# Breakouts0.net
KiCad netlist of a schematic drawn in EAGLE
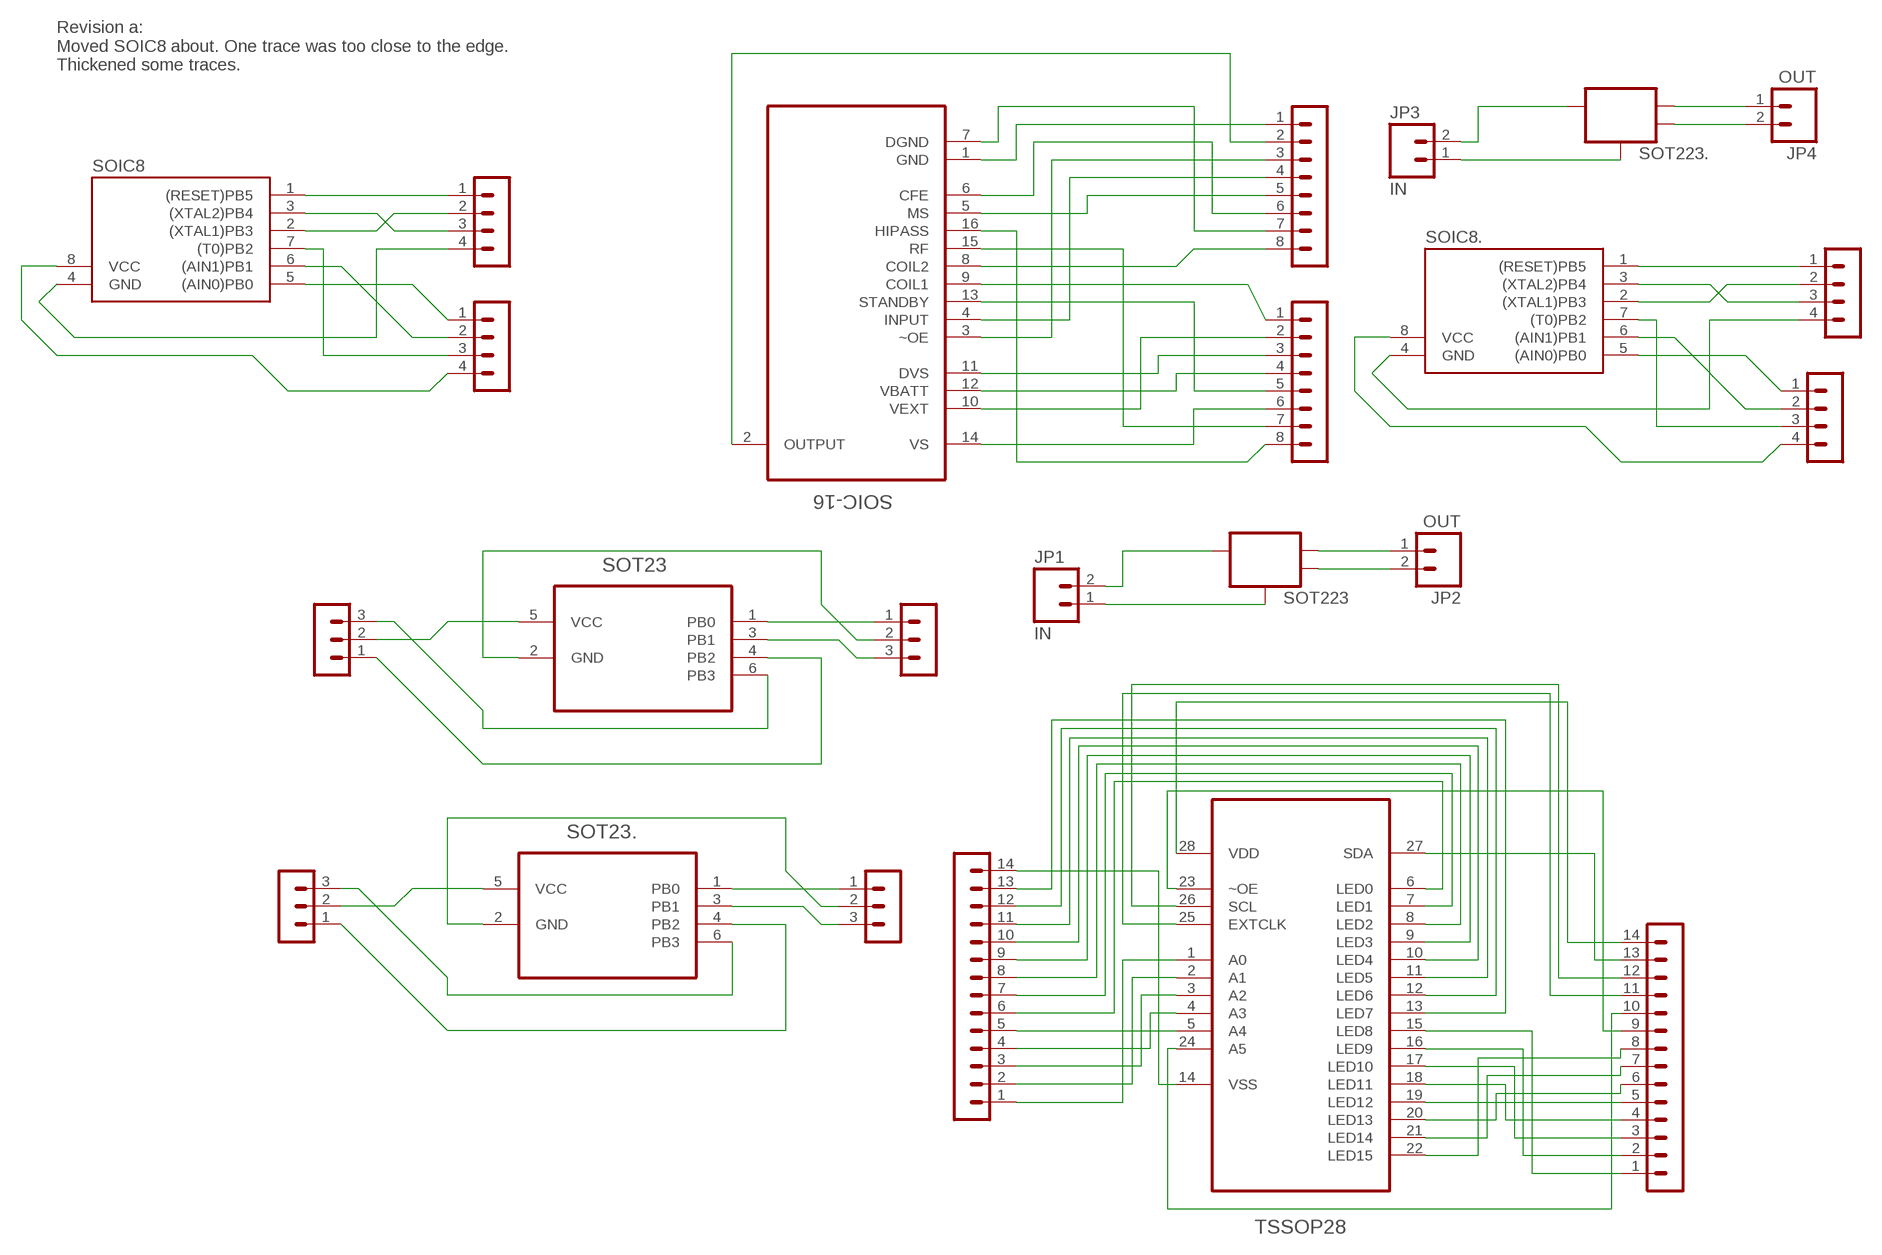
[diagram p0: schematic, sheet 1]

(export (version "E")
  (design (tool "Eeschema 10.0.6"))
  (components
    (comp (ref "JP1")
      (value "IN")
      (footprint "eagle-import:1X02")
      (libsource (lib "eagle-import") (part "M02PTH"))
    )
    (comp (ref "JP2")
      (value "OUT")
      (footprint "eagle-import:1X02")
      (libsource (lib "eagle-import") (part "M02PTH"))
    )
    (comp (ref "JP3")
      (value "IN")
      (footprint "eagle-import:1X02")
      (libsource (lib "eagle-import") (part "M02PTH"))
    )
    (comp (ref "JP4")
      (value "OUT")
      (footprint "eagle-import:1X02")
      (libsource (lib "eagle-import") (part "M02PTH"))
    )
    (comp (ref "SOIC-16")
      (value "U2270B-MFPY")
      (footprint "eagle-import:SOIC127P600X140-16N")
      (libsource (lib "eagle-import") (part "U2270B-MFPY"))
    )
    (comp (ref "SOIC8")
      (value "TINY10S")
      (footprint "eagle-import:SOIC8")
      (libsource (lib "eagle-import") (part "TINY10S"))
    )
    (comp (ref "SOIC8.")
      (value "TINY10S")
      (footprint "eagle-import:SOIC8")
      (libsource (lib "eagle-import") (part "TINY10S"))
    )
    (comp (ref "SOT23")
      (value "ATTINY10-TSHR")
      (footprint "eagle-import:SOT95P280X145-6N")
      (libsource (lib "eagle-import") (part "ATTINY10-TSHR"))
    )
    (comp (ref "SOT23.")
      (value "ATTINY10-TSHR")
      (footprint "eagle-import:SOT95P280X145-6N")
      (libsource (lib "eagle-import") (part "ATTINY10-TSHR"))
    )
    (comp (ref "SOT223")
      (value "SOT223SOT223")
      (footprint "eagle-import:SOT223")
      (libsource (lib "eagle-import") (part "SOT223SOT223"))
    )
    (comp (ref "SOT223.")
      (value "SOT223SOT223")
      (footprint "eagle-import:SOT223")
      (libsource (lib "eagle-import") (part "SOT223SOT223"))
    )
    (comp (ref "SV1")
      (value "MA08-1")
      (footprint "eagle-import:MA08-1")
      (libsource (lib "eagle-import") (part "MA08-1"))
    )
    (comp (ref "SV2")
      (value "MA08-1")
      (footprint "eagle-import:MA08-1")
      (libsource (lib "eagle-import") (part "MA08-1"))
    )
    (comp (ref "SV3")
      (value "MA03-1")
      (footprint "eagle-import:MA03-1")
      (libsource (lib "eagle-import") (part "MA03-1"))
    )
    (comp (ref "SV4")
      (value "MA03-1")
      (footprint "eagle-import:MA03-1")
      (libsource (lib "eagle-import") (part "MA03-1"))
    )
    (comp (ref "SV5")
      (value "MA14-1")
      (footprint "eagle-import:MA14-1")
      (libsource (lib "eagle-import") (part "MA14-1"))
    )
    (comp (ref "SV8")
      (value "MA04-1")
      (footprint "eagle-import:MA04-1")
      (libsource (lib "eagle-import") (part "MA04-1"))
    )
    (comp (ref "SV9")
      (value "MA14-1")
      (footprint "eagle-import:MA14-1")
      (libsource (lib "eagle-import") (part "MA14-1"))
    )
    (comp (ref "SV10")
      (value "MA04-1")
      (footprint "eagle-import:MA04-1")
      (libsource (lib "eagle-import") (part "MA04-1"))
    )
    (comp (ref "SV13")
      (value "MA04-1")
      (footprint "eagle-import:MA04-1")
      (libsource (lib "eagle-import") (part "MA04-1"))
    )
    (comp (ref "SV14")
      (value "MA04-1")
      (footprint "eagle-import:MA04-1")
      (libsource (lib "eagle-import") (part "MA04-1"))
    )
    (comp (ref "SV21")
      (value "MA03-1")
      (footprint "eagle-import:MA03-1")
      (libsource (lib "eagle-import") (part "MA03-1"))
    )
    (comp (ref "SV22")
      (value "MA03-1")
      (footprint "eagle-import:MA03-1")
      (libsource (lib "eagle-import") (part "MA03-1"))
    )
    (comp (ref "TSSOP28")
      (value "PCA9685PW")
      (footprint "eagle-import:SOP65P640X110-28N")
      (libsource (lib "eagle-import") (part "PCA9685PW"))
    )
  )
  (nets
    (net (code "1") (name "Net-(JP2-Pad1)") (class "Default")
      (node (ref "JP2") (pin "1") (pinfunction "1_1") (pintype "passive"))
      (node (ref "SOT223") (pin "2") (pinfunction "OUT_2") (pintype "output"))
    )
    (net (code "2") (name "Net-(JP2-Pad2)") (class "Default")
      (node (ref "JP2") (pin "2") (pinfunction "2_2") (pintype "passive"))
      (node (ref "SOT223") (pin "4") (pinfunction "OUT_4") (pintype "output"))
    )
    (net (code "3") (name "Net-(JP4-Pad1)") (class "Default")
      (node (ref "JP4") (pin "1") (pinfunction "1_1") (pintype "passive"))
      (node (ref "SOT223.") (pin "2") (pinfunction "OUT_2") (pintype "output"))
    )
    (net (code "4") (name "Net-(JP4-Pad2)") (class "Default")
      (node (ref "JP4") (pin "2") (pinfunction "2_2") (pintype "passive"))
      (node (ref "SOT223.") (pin "4") (pinfunction "OUT_4") (pintype "output"))
    )
    (net (code "5") (name "Net-(SOIC-16-CFE)") (class "Default")
      (node (ref "SOIC-16") (pin "6") (pinfunction "CFE_6") (pintype "input"))
      (node (ref "SV1") (pin "6") (pinfunction "6_6") (pintype "passive"))
    )
    (net (code "6") (name "Net-(SOIC-16-COIL1)") (class "Default")
      (node (ref "SOIC-16") (pin "9") (pinfunction "COIL1_9") (pintype "passive"))
      (node (ref "SV2") (pin "1") (pinfunction "1_1") (pintype "passive"))
    )
    (net (code "7") (name "Net-(SOIC-16-COIL2)") (class "Default")
      (node (ref "SOIC-16") (pin "8") (pinfunction "COIL2_8") (pintype "passive"))
      (node (ref "SV1") (pin "8") (pinfunction "8_8") (pintype "passive"))
    )
    (net (code "8") (name "Net-(SOIC-16-DGND)") (class "Default")
      (node (ref "SOIC-16") (pin "7") (pinfunction "DGND_7") (pintype "passive"))
      (node (ref "SV1") (pin "7") (pinfunction "7_7") (pintype "passive"))
    )
    (net (code "9") (name "Net-(SOIC-16-DVS)") (class "Default")
      (node (ref "SOIC-16") (pin "11") (pinfunction "DVS_11") (pintype "power_in"))
      (node (ref "SV2") (pin "3") (pinfunction "3_3") (pintype "passive"))
    )
    (net (code "10") (name "Net-(SOIC-16-GND)") (class "Default")
      (node (ref "SOIC-16") (pin "1") (pinfunction "GND_1") (pintype "passive"))
      (node (ref "SV1") (pin "1") (pinfunction "1_1") (pintype "passive"))
    )
    (net (code "11") (name "Net-(SOIC-16-HIPASS)") (class "Default")
      (node (ref "SOIC-16") (pin "16") (pinfunction "HIPASS_16") (pintype "input"))
      (node (ref "SV2") (pin "8") (pinfunction "8_8") (pintype "passive"))
    )
    (net (code "12") (name "Net-(SOIC-16-INPUT)") (class "Default")
      (node (ref "SOIC-16") (pin "4") (pinfunction "INPUT_4") (pintype "input"))
      (node (ref "SV1") (pin "4") (pinfunction "4_4") (pintype "passive"))
    )
    (net (code "13") (name "Net-(SOIC-16-MS)") (class "Default")
      (node (ref "SOIC-16") (pin "5") (pinfunction "MS_5") (pintype "bidirectional"))
      (node (ref "SV1") (pin "5") (pinfunction "5_5") (pintype "passive"))
    )
    (net (code "14") (name "Net-(SOIC-16-OUTPUT)") (class "Default")
      (node (ref "SOIC-16") (pin "2") (pinfunction "OUTPUT_2") (pintype "output"))
      (node (ref "SV1") (pin "2") (pinfunction "2_2") (pintype "passive"))
    )
    (net (code "15") (name "Net-(SOIC-16-RF)") (class "Default")
      (node (ref "SOIC-16") (pin "15") (pinfunction "RF_15") (pintype "input"))
      (node (ref "SV2") (pin "7") (pinfunction "7_7") (pintype "passive"))
    )
    (net (code "16") (name "Net-(SOIC-16-STANDBY)") (class "Default")
      (node (ref "SOIC-16") (pin "13") (pinfunction "STANDBY_13") (pintype "input"))
      (node (ref "SV2") (pin "5") (pinfunction "5_5") (pintype "passive"))
    )
    (net (code "17") (name "Net-(SOIC-16-VBATT)") (class "Default")
      (node (ref "SOIC-16") (pin "12") (pinfunction "VBATT_12") (pintype "power_in"))
      (node (ref "SV2") (pin "4") (pinfunction "4_4") (pintype "passive"))
    )
    (net (code "18") (name "Net-(SOIC-16-VEXT)") (class "Default")
      (node (ref "SOIC-16") (pin "10") (pinfunction "VEXT_10") (pintype "power_in"))
      (node (ref "SV2") (pin "2") (pinfunction "2_2") (pintype "passive"))
    )
    (net (code "19") (name "Net-(SOIC-16-VS)") (class "Default")
      (node (ref "SOIC-16") (pin "14") (pinfunction "VS_14") (pintype "power_in"))
      (node (ref "SV2") (pin "6") (pinfunction "6_6") (pintype "passive"))
    )
    (net (code "20") (name "Net-(SOIC-16-~{OE})") (class "Default")
      (node (ref "SOIC-16") (pin "3") (pinfunction "~{OE}_3") (pintype "input"))
      (node (ref "SV1") (pin "3") (pinfunction "3_3") (pintype "passive"))
    )
    (net (code "21") (name "Net-(SOIC8-(AIN0)PB0)") (class "Default")
      (node (ref "SOIC8") (pin "5") (pinfunction "(AIN0)PB0_5") (pintype "bidirectional"))
      (node (ref "SV14") (pin "1") (pinfunction "1_1") (pintype "passive"))
    )
    (net (code "22") (name "Net-(SOIC8-(AIN1)PB1)") (class "Default")
      (node (ref "SOIC8") (pin "6") (pinfunction "(AIN1)PB1_6") (pintype "bidirectional"))
      (node (ref "SV14") (pin "2") (pinfunction "2_2") (pintype "passive"))
    )
    (net (code "23") (name "Net-(SOIC8-(RESET)PB5)") (class "Default")
      (node (ref "SOIC8") (pin "1") (pinfunction "(RESET)PB5_1") (pintype "bidirectional"))
      (node (ref "SV13") (pin "1") (pinfunction "1_1") (pintype "passive"))
    )
    (net (code "24") (name "Net-(SOIC8-(T0)PB2)") (class "Default")
      (node (ref "SOIC8") (pin "7") (pinfunction "(T0)PB2_7") (pintype "bidirectional"))
      (node (ref "SV14") (pin "3") (pinfunction "3_3") (pintype "passive"))
    )
    (net (code "25") (name "Net-(SOIC8-(XTAL1)PB3)") (class "Default")
      (node (ref "SOIC8") (pin "2") (pinfunction "(XTAL1)PB3_2") (pintype "bidirectional"))
      (node (ref "SV13") (pin "2") (pinfunction "2_2") (pintype "passive"))
    )
    (net (code "26") (name "Net-(SOIC8-(XTAL2)PB4)") (class "Default")
      (node (ref "SOIC8") (pin "3") (pinfunction "(XTAL2)PB4_3") (pintype "bidirectional"))
      (node (ref "SV13") (pin "3") (pinfunction "3_3") (pintype "passive"))
    )
    (net (code "27") (name "Net-(SOIC8-GND)") (class "Default")
      (node (ref "SOIC8") (pin "4") (pinfunction "GND_4") (pintype "power_in"))
      (node (ref "SV13") (pin "4") (pinfunction "4_4") (pintype "passive"))
    )
    (net (code "28") (name "Net-(SOIC8-VCC)") (class "Default")
      (node (ref "SOIC8") (pin "8") (pinfunction "VCC_8") (pintype "power_in"))
      (node (ref "SV14") (pin "4") (pinfunction "4_4") (pintype "passive"))
    )
    (net (code "29") (name "Net-(SOIC8.-(AIN0)PB0)") (class "Default")
      (node (ref "SOIC8.") (pin "5") (pinfunction "(AIN0)PB0_5") (pintype "bidirectional"))
      (node (ref "SV10") (pin "1") (pinfunction "1_1") (pintype "passive"))
    )
    (net (code "30") (name "Net-(SOIC8.-(AIN1)PB1)") (class "Default")
      (node (ref "SOIC8.") (pin "6") (pinfunction "(AIN1)PB1_6") (pintype "bidirectional"))
      (node (ref "SV10") (pin "2") (pinfunction "2_2") (pintype "passive"))
    )
    (net (code "31") (name "Net-(SOIC8.-(RESET)PB5)") (class "Default")
      (node (ref "SOIC8.") (pin "1") (pinfunction "(RESET)PB5_1") (pintype "bidirectional"))
      (node (ref "SV8") (pin "1") (pinfunction "1_1") (pintype "passive"))
    )
    (net (code "32") (name "Net-(SOIC8.-(T0)PB2)") (class "Default")
      (node (ref "SOIC8.") (pin "7") (pinfunction "(T0)PB2_7") (pintype "bidirectional"))
      (node (ref "SV10") (pin "3") (pinfunction "3_3") (pintype "passive"))
    )
    (net (code "33") (name "Net-(SOIC8.-(XTAL1)PB3)") (class "Default")
      (node (ref "SOIC8.") (pin "2") (pinfunction "(XTAL1)PB3_2") (pintype "bidirectional"))
      (node (ref "SV8") (pin "2") (pinfunction "2_2") (pintype "passive"))
    )
    (net (code "34") (name "Net-(SOIC8.-(XTAL2)PB4)") (class "Default")
      (node (ref "SOIC8.") (pin "3") (pinfunction "(XTAL2)PB4_3") (pintype "bidirectional"))
      (node (ref "SV8") (pin "3") (pinfunction "3_3") (pintype "passive"))
    )
    (net (code "35") (name "Net-(SOIC8.-GND)") (class "Default")
      (node (ref "SOIC8.") (pin "4") (pinfunction "GND_4") (pintype "power_in"))
      (node (ref "SV8") (pin "4") (pinfunction "4_4") (pintype "passive"))
    )
    (net (code "36") (name "Net-(SOIC8.-VCC)") (class "Default")
      (node (ref "SOIC8.") (pin "8") (pinfunction "VCC_8") (pintype "power_in"))
      (node (ref "SV10") (pin "4") (pinfunction "4_4") (pintype "passive"))
    )
    (net (code "37") (name "Net-(SOT23-GND)") (class "Default")
      (node (ref "SOT23") (pin "2") (pinfunction "GND_2") (pintype "passive"))
      (node (ref "SV22") (pin "2") (pinfunction "2_2") (pintype "passive"))
    )
    (net (code "38") (name "Net-(SOT23-PB0)") (class "Default")
      (node (ref "SOT23") (pin "1") (pinfunction "PB0_1") (pintype "bidirectional"))
      (node (ref "SV22") (pin "1") (pinfunction "1_1") (pintype "passive"))
    )
    (net (code "39") (name "Net-(SOT23-PB1)") (class "Default")
      (node (ref "SOT23") (pin "3") (pinfunction "PB1_3") (pintype "bidirectional"))
      (node (ref "SV22") (pin "3") (pinfunction "3_3") (pintype "passive"))
    )
    (net (code "40") (name "Net-(SOT23-PB2)") (class "Default")
      (node (ref "SOT23") (pin "4") (pinfunction "PB2_4") (pintype "bidirectional"))
      (node (ref "SV21") (pin "1") (pinfunction "1_1") (pintype "passive"))
    )
    (net (code "41") (name "Net-(SOT23-PB3)") (class "Default")
      (node (ref "SOT23") (pin "6") (pinfunction "PB3_6") (pintype "bidirectional"))
      (node (ref "SV21") (pin "3") (pinfunction "3_3") (pintype "passive"))
    )
    (net (code "42") (name "Net-(SOT23-VCC)") (class "Default")
      (node (ref "SOT23") (pin "5") (pinfunction "VCC_5") (pintype "power_in"))
      (node (ref "SV21") (pin "2") (pinfunction "2_2") (pintype "passive"))
    )
    (net (code "43") (name "Net-(SOT23.-GND)") (class "Default")
      (node (ref "SOT23.") (pin "2") (pinfunction "GND_2") (pintype "passive"))
      (node (ref "SV4") (pin "2") (pinfunction "2_2") (pintype "passive"))
    )
    (net (code "44") (name "Net-(SOT23.-PB0)") (class "Default")
      (node (ref "SOT23.") (pin "1") (pinfunction "PB0_1") (pintype "bidirectional"))
      (node (ref "SV4") (pin "1") (pinfunction "1_1") (pintype "passive"))
    )
    (net (code "45") (name "Net-(SOT23.-PB1)") (class "Default")
      (node (ref "SOT23.") (pin "3") (pinfunction "PB1_3") (pintype "bidirectional"))
      (node (ref "SV4") (pin "3") (pinfunction "3_3") (pintype "passive"))
    )
    (net (code "46") (name "Net-(SOT23.-PB2)") (class "Default")
      (node (ref "SOT23.") (pin "4") (pinfunction "PB2_4") (pintype "bidirectional"))
      (node (ref "SV3") (pin "1") (pinfunction "1_1") (pintype "passive"))
    )
    (net (code "47") (name "Net-(SOT23.-PB3)") (class "Default")
      (node (ref "SOT23.") (pin "6") (pinfunction "PB3_6") (pintype "bidirectional"))
      (node (ref "SV3") (pin "3") (pinfunction "3_3") (pintype "passive"))
    )
    (net (code "48") (name "Net-(SOT23.-VCC)") (class "Default")
      (node (ref "SOT23.") (pin "5") (pinfunction "VCC_5") (pintype "power_in"))
      (node (ref "SV3") (pin "2") (pinfunction "2_2") (pintype "passive"))
    )
    (net (code "49") (name "Net-(SOT223-ADJ)") (class "Default")
      (node (ref "JP1") (pin "1") (pinfunction "1_1") (pintype "passive"))
      (node (ref "SOT223") (pin "1") (pinfunction "ADJ_1") (pintype "input"))
    )
    (net (code "50") (name "Net-(SOT223-IN)") (class "Default")
      (node (ref "JP1") (pin "2") (pinfunction "2_2") (pintype "passive"))
      (node (ref "SOT223") (pin "3") (pinfunction "IN_3") (pintype "input"))
    )
    (net (code "51") (name "Net-(SOT223.-ADJ)") (class "Default")
      (node (ref "JP3") (pin "1") (pinfunction "1_1") (pintype "passive"))
      (node (ref "SOT223.") (pin "1") (pinfunction "ADJ_1") (pintype "input"))
    )
    (net (code "52") (name "Net-(SOT223.-IN)") (class "Default")
      (node (ref "JP3") (pin "2") (pinfunction "2_2") (pintype "passive"))
      (node (ref "SOT223.") (pin "3") (pinfunction "IN_3") (pintype "input"))
    )
    (net (code "53") (name "Net-(TSSOP28-A0)") (class "Default")
      (node (ref "SV5") (pin "1") (pinfunction "1_1") (pintype "passive"))
      (node (ref "TSSOP28") (pin "1") (pinfunction "A0_1") (pintype "input"))
    )
    (net (code "54") (name "Net-(TSSOP28-A1)") (class "Default")
      (node (ref "SV5") (pin "2") (pinfunction "2_2") (pintype "passive"))
      (node (ref "TSSOP28") (pin "2") (pinfunction "A1_2") (pintype "input"))
    )
    (net (code "55") (name "Net-(TSSOP28-A2)") (class "Default")
      (node (ref "SV5") (pin "3") (pinfunction "3_3") (pintype "passive"))
      (node (ref "TSSOP28") (pin "3") (pinfunction "A2_3") (pintype "input"))
    )
    (net (code "56") (name "Net-(TSSOP28-A3)") (class "Default")
      (node (ref "SV5") (pin "4") (pinfunction "4_4") (pintype "passive"))
      (node (ref "TSSOP28") (pin "4") (pinfunction "A3_4") (pintype "input"))
    )
    (net (code "57") (name "Net-(TSSOP28-A4)") (class "Default")
      (node (ref "SV5") (pin "5") (pinfunction "5_5") (pintype "passive"))
      (node (ref "TSSOP28") (pin "5") (pinfunction "A4_5") (pintype "input"))
    )
    (net (code "58") (name "Net-(TSSOP28-A5)") (class "Default")
      (node (ref "SV9") (pin "10") (pinfunction "10_10") (pintype "passive"))
      (node (ref "TSSOP28") (pin "24") (pinfunction "A5_24") (pintype "input"))
    )
    (net (code "59") (name "Net-(TSSOP28-EXTCLK)") (class "Default")
      (node (ref "SV9") (pin "11") (pinfunction "11_11") (pintype "passive"))
      (node (ref "TSSOP28") (pin "25") (pinfunction "EXTCLK_25") (pintype "input"))
    )
    (net (code "60") (name "Net-(TSSOP28-LED0)") (class "Default")
      (node (ref "SV5") (pin "6") (pinfunction "6_6") (pintype "passive"))
      (node (ref "TSSOP28") (pin "6") (pinfunction "LED0_6") (pintype "output"))
    )
    (net (code "61") (name "Net-(TSSOP28-LED1)") (class "Default")
      (node (ref "SV5") (pin "7") (pinfunction "7_7") (pintype "passive"))
      (node (ref "TSSOP28") (pin "7") (pinfunction "LED1_7") (pintype "output"))
    )
    (net (code "62") (name "Net-(TSSOP28-LED2)") (class "Default")
      (node (ref "SV5") (pin "8") (pinfunction "8_8") (pintype "passive"))
      (node (ref "TSSOP28") (pin "8") (pinfunction "LED2_8") (pintype "output"))
    )
    (net (code "63") (name "Net-(TSSOP28-LED3)") (class "Default")
      (node (ref "SV5") (pin "9") (pinfunction "9_9") (pintype "passive"))
      (node (ref "TSSOP28") (pin "9") (pinfunction "LED3_9") (pintype "output"))
    )
    (net (code "64") (name "Net-(TSSOP28-LED4)") (class "Default")
      (node (ref "SV5") (pin "10") (pinfunction "10_10") (pintype "passive"))
      (node (ref "TSSOP28") (pin "10") (pinfunction "LED4_10") (pintype "output"))
    )
    (net (code "65") (name "Net-(TSSOP28-LED5)") (class "Default")
      (node (ref "SV5") (pin "11") (pinfunction "11_11") (pintype "passive"))
      (node (ref "TSSOP28") (pin "11") (pinfunction "LED5_11") (pintype "output"))
    )
    (net (code "66") (name "Net-(TSSOP28-LED6)") (class "Default")
      (node (ref "SV5") (pin "12") (pinfunction "12_12") (pintype "passive"))
      (node (ref "TSSOP28") (pin "12") (pinfunction "LED6_12") (pintype "output"))
    )
    (net (code "67") (name "Net-(TSSOP28-LED7)") (class "Default")
      (node (ref "SV5") (pin "13") (pinfunction "13_13") (pintype "passive"))
      (node (ref "TSSOP28") (pin "13") (pinfunction "LED7_13") (pintype "output"))
    )
    (net (code "68") (name "Net-(TSSOP28-LED8)") (class "Default")
      (node (ref "SV9") (pin "1") (pinfunction "1_1") (pintype "passive"))
      (node (ref "TSSOP28") (pin "15") (pinfunction "LED8_15") (pintype "output"))
    )
    (net (code "69") (name "Net-(TSSOP28-LED9)") (class "Default")
      (node (ref "SV9") (pin "2") (pinfunction "2_2") (pintype "passive"))
      (node (ref "TSSOP28") (pin "16") (pinfunction "LED9_16") (pintype "output"))
    )
    (net (code "70") (name "Net-(TSSOP28-LED10)") (class "Default")
      (node (ref "SV9") (pin "3") (pinfunction "3_3") (pintype "passive"))
      (node (ref "TSSOP28") (pin "17") (pinfunction "LED10_17") (pintype "output"))
    )
    (net (code "71") (name "Net-(TSSOP28-LED11)") (class "Default")
      (node (ref "SV9") (pin "4") (pinfunction "4_4") (pintype "passive"))
      (node (ref "TSSOP28") (pin "18") (pinfunction "LED11_18") (pintype "output"))
    )
    (net (code "72") (name "Net-(TSSOP28-LED12)") (class "Default")
      (node (ref "SV9") (pin "5") (pinfunction "5_5") (pintype "passive"))
      (node (ref "TSSOP28") (pin "19") (pinfunction "LED12_19") (pintype "output"))
    )
    (net (code "73") (name "Net-(TSSOP28-LED13)") (class "Default")
      (node (ref "SV9") (pin "6") (pinfunction "6_6") (pintype "passive"))
      (node (ref "TSSOP28") (pin "20") (pinfunction "LED13_20") (pintype "output"))
    )
    (net (code "74") (name "Net-(TSSOP28-LED14)") (class "Default")
      (node (ref "SV9") (pin "7") (pinfunction "7_7") (pintype "passive"))
      (node (ref "TSSOP28") (pin "21") (pinfunction "LED14_21") (pintype "output"))
    )
    (net (code "75") (name "Net-(TSSOP28-LED15)") (class "Default")
      (node (ref "SV9") (pin "8") (pinfunction "8_8") (pintype "passive"))
      (node (ref "TSSOP28") (pin "22") (pinfunction "LED15_22") (pintype "output"))
    )
    (net (code "76") (name "Net-(TSSOP28-SCL)") (class "Default")
      (node (ref "SV9") (pin "12") (pinfunction "12_12") (pintype "passive"))
      (node (ref "TSSOP28") (pin "26") (pinfunction "SCL_26") (pintype "input"))
    )
    (net (code "77") (name "Net-(TSSOP28-SDA)") (class "Default")
      (node (ref "SV9") (pin "13") (pinfunction "13_13") (pintype "passive"))
      (node (ref "TSSOP28") (pin "27") (pinfunction "SDA_27") (pintype "bidirectional"))
    )
    (net (code "78") (name "Net-(TSSOP28-VDD)") (class "Default")
      (node (ref "SV9") (pin "14") (pinfunction "14_14") (pintype "passive"))
      (node (ref "TSSOP28") (pin "28") (pinfunction "VDD_28") (pintype "power_in"))
    )
    (net (code "79") (name "Net-(TSSOP28-VSS)") (class "Default")
      (node (ref "SV5") (pin "14") (pinfunction "14_14") (pintype "passive"))
      (node (ref "TSSOP28") (pin "14") (pinfunction "VSS_14") (pintype "passive"))
    )
    (net (code "80") (name "Net-(TSSOP28-~{OE})") (class "Default")
      (node (ref "SV9") (pin "9") (pinfunction "9_9") (pintype "passive"))
      (node (ref "TSSOP28") (pin "23") (pinfunction "~{OE}_23") (pintype "input"))
    )
  )
)
